# gpio_expander.net
KiCad netlist of a schematic drawn in EAGLE
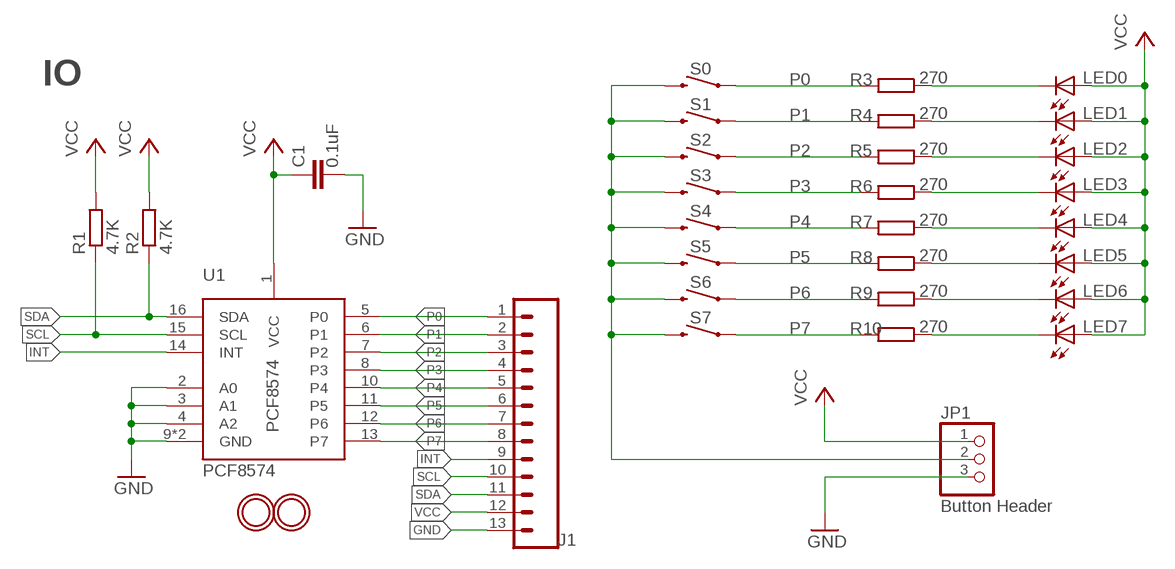
[diagram p0: schematic, sheet 1]

(export (version "E")
  (design (tool "Eeschema 10.0.6"))
  (components
    (comp (ref "C1")
      (value "0.1uF")
      (footprint "eagle-import:C0805K")
      (libsource (lib "eagle-import") (part "C-EUC0805K"))
    )
    (comp (ref "J1")
      (value "GPIO Expander Pins")
      (footprint "eagle-import:1X13_NO_SILK")
      (libsource (lib "eagle-import") (part "CONN_13"))
    )
    (comp (ref "JP1")
      (value "Button Header")
      (footprint "eagle-import:1X03")
      (libsource (lib "eagle-import") (part "PINHD-1X3"))
    )
    (comp (ref "LED0")
      (value "GREEN")
      (footprint "eagle-import:CHIP-LED0805")
      (libsource (lib "eagle-import") (part "LEDCHIP-LED0805"))
    )
    (comp (ref "LED1")
      (value "GREEN")
      (footprint "eagle-import:CHIP-LED0805")
      (libsource (lib "eagle-import") (part "LEDCHIP-LED0805"))
    )
    (comp (ref "LED2")
      (value "GREEN")
      (footprint "eagle-import:CHIP-LED0805")
      (libsource (lib "eagle-import") (part "LEDCHIP-LED0805"))
    )
    (comp (ref "LED3")
      (value "GREEN")
      (footprint "eagle-import:CHIP-LED0805")
      (libsource (lib "eagle-import") (part "LEDCHIP-LED0805"))
    )
    (comp (ref "LED4")
      (value "GREEN")
      (footprint "eagle-import:CHIP-LED0805")
      (libsource (lib "eagle-import") (part "LEDCHIP-LED0805"))
    )
    (comp (ref "LED5")
      (value "GREEN")
      (footprint "eagle-import:CHIP-LED0805")
      (libsource (lib "eagle-import") (part "LEDCHIP-LED0805"))
    )
    (comp (ref "LED6")
      (value "GREEN")
      (footprint "eagle-import:CHIP-LED0805")
      (libsource (lib "eagle-import") (part "LEDCHIP-LED0805"))
    )
    (comp (ref "LED7")
      (value "GREEN")
      (footprint "eagle-import:CHIP-LED0805")
      (libsource (lib "eagle-import") (part "LEDCHIP-LED0805"))
    )
    (comp (ref "MH1")
      (value "MOUNTINGHOLE2.5")
      (footprint "eagle-import:MOUNTINGHOLE_2.5_PLATED")
      (libsource (lib "eagle-import") (part "MOUNTINGHOLE2.5"))
    )
    (comp (ref "MH3")
      (value "MOUNTINGHOLE2.5")
      (footprint "eagle-import:MOUNTINGHOLE_2.5_PLATED")
      (libsource (lib "eagle-import") (part "MOUNTINGHOLE2.5"))
    )
    (comp (ref "R1")
      (value "4.7K")
      (footprint "eagle-import:R0805")
      (libsource (lib "eagle-import") (part "R-EU_R0805"))
    )
    (comp (ref "R2")
      (value "4.7K")
      (footprint "eagle-import:R0805")
      (libsource (lib "eagle-import") (part "R-EU_R0805"))
    )
    (comp (ref "R3")
      (value "270")
      (footprint "eagle-import:R0805")
      (libsource (lib "eagle-import") (part "R-EU_R0805"))
    )
    (comp (ref "R4")
      (value "270")
      (footprint "eagle-import:R0805")
      (libsource (lib "eagle-import") (part "R-EU_R0805"))
    )
    (comp (ref "R5")
      (value "270")
      (footprint "eagle-import:R0805")
      (libsource (lib "eagle-import") (part "R-EU_R0805"))
    )
    (comp (ref "R6")
      (value "270")
      (footprint "eagle-import:R0805")
      (libsource (lib "eagle-import") (part "R-EU_R0805"))
    )
    (comp (ref "R7")
      (value "270")
      (footprint "eagle-import:R0805")
      (libsource (lib "eagle-import") (part "R-EU_R0805"))
    )
    (comp (ref "R8")
      (value "270")
      (footprint "eagle-import:R0805")
      (libsource (lib "eagle-import") (part "R-EU_R0805"))
    )
    (comp (ref "R9")
      (value "270")
      (footprint "eagle-import:R0805")
      (libsource (lib "eagle-import") (part "R-EU_R0805"))
    )
    (comp (ref "R10")
      (value "270")
      (footprint "eagle-import:R0805")
      (libsource (lib "eagle-import") (part "R-EU_R0805"))
    )
    (comp (ref "S0")
      (value "MOMENTARY-SWITCH-SPST-SMD-4.6X2.8MM")
      (footprint "eagle-import:TACTILE_SWITCH_SMD_4.6X2.8MM")
      (libsource (lib "eagle-import") (part "MOMENTARY-SWITCH-SPST-SMD-4.6X2.8MM"))
    )
    (comp (ref "S1")
      (value "MOMENTARY-SWITCH-SPST-SMD-4.6X2.8MM")
      (footprint "eagle-import:TACTILE_SWITCH_SMD_4.6X2.8MM")
      (libsource (lib "eagle-import") (part "MOMENTARY-SWITCH-SPST-SMD-4.6X2.8MM"))
    )
    (comp (ref "S2")
      (value "MOMENTARY-SWITCH-SPST-SMD-4.6X2.8MM")
      (footprint "eagle-import:TACTILE_SWITCH_SMD_4.6X2.8MM")
      (libsource (lib "eagle-import") (part "MOMENTARY-SWITCH-SPST-SMD-4.6X2.8MM"))
    )
    (comp (ref "S3")
      (value "MOMENTARY-SWITCH-SPST-SMD-4.6X2.8MM")
      (footprint "eagle-import:TACTILE_SWITCH_SMD_4.6X2.8MM")
      (libsource (lib "eagle-import") (part "MOMENTARY-SWITCH-SPST-SMD-4.6X2.8MM"))
    )
    (comp (ref "S4")
      (value "MOMENTARY-SWITCH-SPST-SMD-4.6X2.8MM")
      (footprint "eagle-import:TACTILE_SWITCH_SMD_4.6X2.8MM")
      (libsource (lib "eagle-import") (part "MOMENTARY-SWITCH-SPST-SMD-4.6X2.8MM"))
    )
    (comp (ref "S5")
      (value "MOMENTARY-SWITCH-SPST-SMD-4.6X2.8MM")
      (footprint "eagle-import:TACTILE_SWITCH_SMD_4.6X2.8MM")
      (libsource (lib "eagle-import") (part "MOMENTARY-SWITCH-SPST-SMD-4.6X2.8MM"))
    )
    (comp (ref "S6")
      (value "MOMENTARY-SWITCH-SPST-SMD-4.6X2.8MM")
      (footprint "eagle-import:TACTILE_SWITCH_SMD_4.6X2.8MM")
      (libsource (lib "eagle-import") (part "MOMENTARY-SWITCH-SPST-SMD-4.6X2.8MM"))
    )
    (comp (ref "S7")
      (value "MOMENTARY-SWITCH-SPST-SMD-4.6X2.8MM")
      (footprint "eagle-import:TACTILE_SWITCH_SMD_4.6X2.8MM")
      (libsource (lib "eagle-import") (part "MOMENTARY-SWITCH-SPST-SMD-4.6X2.8MM"))
    )
    (comp (ref "U1")
      (value "PCF8574")
      (footprint "eagle-import:QFN-16-3MM")
      (libsource (lib "eagle-import") (part "PCF8574"))
    )
  )
  (nets
    (net (code "1") (name "GND") (class "Default")
      (node (ref "C1") (pin "2") (pinfunction "2_2") (pintype "passive"))
      (node (ref "J1") (pin "13") (pinfunction "13_13") (pintype "passive"))
      (node (ref "JP1") (pin "3") (pinfunction "3_3") (pintype "passive"))
      (node (ref "U1") (pin "2") (pinfunction "A0_2") (pintype "bidirectional"))
      (node (ref "U1") (pin "3") (pinfunction "A1_3") (pintype "bidirectional"))
      (node (ref "U1") (pin "4") (pinfunction "A2_4") (pintype "bidirectional"))
      (node (ref "U1") (pin "9") (pinfunction "GND_9") (pintype "bidirectional"))
      (node (ref "U1") (pin "P$1") (pinfunction "GND_P$1") (pintype "bidirectional"))
    )
    (net (code "2") (name "INT") (class "Default")
      (node (ref "J1") (pin "9") (pinfunction "9_9") (pintype "passive"))
      (node (ref "U1") (pin "14") (pinfunction "INT_14") (pintype "bidirectional"))
    )
    (net (code "3") (name "Net-(JP1-Pad2)") (class "Default")
      (node (ref "JP1") (pin "2") (pinfunction "2_2") (pintype "passive"))
      (node (ref "S0") (pin "3") (pinfunction "2_3") (pintype "passive"))
      (node (ref "S0") (pin "4") (pinfunction "2_4") (pintype "passive"))
      (node (ref "S1") (pin "3") (pinfunction "2_3") (pintype "passive"))
      (node (ref "S1") (pin "4") (pinfunction "2_4") (pintype "passive"))
      (node (ref "S2") (pin "3") (pinfunction "2_3") (pintype "passive"))
      (node (ref "S2") (pin "4") (pinfunction "2_4") (pintype "passive"))
      (node (ref "S3") (pin "3") (pinfunction "2_3") (pintype "passive"))
      (node (ref "S3") (pin "4") (pinfunction "2_4") (pintype "passive"))
      (node (ref "S4") (pin "3") (pinfunction "2_3") (pintype "passive"))
      (node (ref "S4") (pin "4") (pinfunction "2_4") (pintype "passive"))
      (node (ref "S5") (pin "3") (pinfunction "2_3") (pintype "passive"))
      (node (ref "S5") (pin "4") (pinfunction "2_4") (pintype "passive"))
      (node (ref "S6") (pin "3") (pinfunction "2_3") (pintype "passive"))
      (node (ref "S6") (pin "4") (pinfunction "2_4") (pintype "passive"))
      (node (ref "S7") (pin "3") (pinfunction "2_3") (pintype "passive"))
      (node (ref "S7") (pin "4") (pinfunction "2_4") (pintype "passive"))
    )
    (net (code "4") (name "Net-(LED0-PadC)") (class "Default")
      (node (ref "LED0") (pin "C") (pinfunction "C_C") (pintype "passive"))
      (node (ref "R3") (pin "1") (pinfunction "1_1") (pintype "passive"))
    )
    (net (code "5") (name "Net-(LED1-PadC)") (class "Default")
      (node (ref "LED1") (pin "C") (pinfunction "C_C") (pintype "passive"))
      (node (ref "R4") (pin "1") (pinfunction "1_1") (pintype "passive"))
    )
    (net (code "6") (name "Net-(LED2-PadC)") (class "Default")
      (node (ref "LED2") (pin "C") (pinfunction "C_C") (pintype "passive"))
      (node (ref "R5") (pin "1") (pinfunction "1_1") (pintype "passive"))
    )
    (net (code "7") (name "Net-(LED3-PadC)") (class "Default")
      (node (ref "LED3") (pin "C") (pinfunction "C_C") (pintype "passive"))
      (node (ref "R6") (pin "1") (pinfunction "1_1") (pintype "passive"))
    )
    (net (code "8") (name "Net-(LED4-PadC)") (class "Default")
      (node (ref "LED4") (pin "C") (pinfunction "C_C") (pintype "passive"))
      (node (ref "R7") (pin "1") (pinfunction "1_1") (pintype "passive"))
    )
    (net (code "9") (name "Net-(LED5-PadC)") (class "Default")
      (node (ref "LED5") (pin "C") (pinfunction "C_C") (pintype "passive"))
      (node (ref "R8") (pin "1") (pinfunction "1_1") (pintype "passive"))
    )
    (net (code "10") (name "Net-(LED6-PadC)") (class "Default")
      (node (ref "LED6") (pin "C") (pinfunction "C_C") (pintype "passive"))
      (node (ref "R9") (pin "1") (pinfunction "1_1") (pintype "passive"))
    )
    (net (code "11") (name "Net-(LED7-PadC)") (class "Default")
      (node (ref "LED7") (pin "C") (pinfunction "C_C") (pintype "passive"))
      (node (ref "R10") (pin "1") (pinfunction "1_1") (pintype "passive"))
    )
    (net (code "12") (name "P0") (class "Default")
      (node (ref "J1") (pin "1") (pinfunction "1_1") (pintype "passive"))
      (node (ref "R3") (pin "2") (pinfunction "2_2") (pintype "passive"))
      (node (ref "S0") (pin "1") (pinfunction "1_1") (pintype "passive"))
      (node (ref "S0") (pin "2") (pinfunction "1_2") (pintype "passive"))
      (node (ref "U1") (pin "5") (pinfunction "P0_5") (pintype "bidirectional"))
    )
    (net (code "13") (name "P1") (class "Default")
      (node (ref "J1") (pin "2") (pinfunction "2_2") (pintype "passive"))
      (node (ref "R4") (pin "2") (pinfunction "2_2") (pintype "passive"))
      (node (ref "S1") (pin "1") (pinfunction "1_1") (pintype "passive"))
      (node (ref "S1") (pin "2") (pinfunction "1_2") (pintype "passive"))
      (node (ref "U1") (pin "6") (pinfunction "P1_6") (pintype "bidirectional"))
    )
    (net (code "14") (name "P2") (class "Default")
      (node (ref "J1") (pin "3") (pinfunction "3_3") (pintype "passive"))
      (node (ref "R5") (pin "2") (pinfunction "2_2") (pintype "passive"))
      (node (ref "S2") (pin "1") (pinfunction "1_1") (pintype "passive"))
      (node (ref "S2") (pin "2") (pinfunction "1_2") (pintype "passive"))
      (node (ref "U1") (pin "7") (pinfunction "P2_7") (pintype "bidirectional"))
    )
    (net (code "15") (name "P3") (class "Default")
      (node (ref "J1") (pin "4") (pinfunction "4_4") (pintype "passive"))
      (node (ref "R6") (pin "2") (pinfunction "2_2") (pintype "passive"))
      (node (ref "S3") (pin "1") (pinfunction "1_1") (pintype "passive"))
      (node (ref "S3") (pin "2") (pinfunction "1_2") (pintype "passive"))
      (node (ref "U1") (pin "8") (pinfunction "P3_8") (pintype "bidirectional"))
    )
    (net (code "16") (name "P4") (class "Default")
      (node (ref "J1") (pin "5") (pinfunction "5_5") (pintype "passive"))
      (node (ref "R7") (pin "2") (pinfunction "2_2") (pintype "passive"))
      (node (ref "S4") (pin "1") (pinfunction "1_1") (pintype "passive"))
      (node (ref "S4") (pin "2") (pinfunction "1_2") (pintype "passive"))
      (node (ref "U1") (pin "10") (pinfunction "P4_10") (pintype "bidirectional"))
    )
    (net (code "17") (name "P5") (class "Default")
      (node (ref "J1") (pin "6") (pinfunction "6_6") (pintype "passive"))
      (node (ref "R8") (pin "2") (pinfunction "2_2") (pintype "passive"))
      (node (ref "S5") (pin "1") (pinfunction "1_1") (pintype "passive"))
      (node (ref "S5") (pin "2") (pinfunction "1_2") (pintype "passive"))
      (node (ref "U1") (pin "11") (pinfunction "P5_11") (pintype "bidirectional"))
    )
    (net (code "18") (name "P6") (class "Default")
      (node (ref "J1") (pin "7") (pinfunction "7_7") (pintype "passive"))
      (node (ref "R9") (pin "2") (pinfunction "2_2") (pintype "passive"))
      (node (ref "S6") (pin "1") (pinfunction "1_1") (pintype "passive"))
      (node (ref "S6") (pin "2") (pinfunction "1_2") (pintype "passive"))
      (node (ref "U1") (pin "12") (pinfunction "P6_12") (pintype "bidirectional"))
    )
    (net (code "19") (name "P7") (class "Default")
      (node (ref "J1") (pin "8") (pinfunction "8_8") (pintype "passive"))
      (node (ref "R10") (pin "2") (pinfunction "2_2") (pintype "passive"))
      (node (ref "S7") (pin "1") (pinfunction "1_1") (pintype "passive"))
      (node (ref "S7") (pin "2") (pinfunction "1_2") (pintype "passive"))
      (node (ref "U1") (pin "13") (pinfunction "P7_13") (pintype "bidirectional"))
    )
    (net (code "20") (name "SCL") (class "Default")
      (node (ref "J1") (pin "10") (pinfunction "10_10") (pintype "passive"))
      (node (ref "R1") (pin "1") (pinfunction "1_1") (pintype "passive"))
      (node (ref "U1") (pin "15") (pinfunction "SCL_15") (pintype "bidirectional"))
    )
    (net (code "21") (name "SDA") (class "Default")
      (node (ref "J1") (pin "11") (pinfunction "11_11") (pintype "passive"))
      (node (ref "R2") (pin "1") (pinfunction "1_1") (pintype "passive"))
      (node (ref "U1") (pin "16") (pinfunction "SDA_16") (pintype "bidirectional"))
    )
    (net (code "22") (name "VCC") (class "Default")
      (node (ref "C1") (pin "1") (pinfunction "1_1") (pintype "passive"))
      (node (ref "J1") (pin "12") (pinfunction "12_12") (pintype "passive"))
      (node (ref "JP1") (pin "1") (pinfunction "1_1") (pintype "passive"))
      (node (ref "LED0") (pin "A") (pinfunction "A_A") (pintype "passive"))
      (node (ref "LED1") (pin "A") (pinfunction "A_A") (pintype "passive"))
      (node (ref "LED2") (pin "A") (pinfunction "A_A") (pintype "passive"))
      (node (ref "LED3") (pin "A") (pinfunction "A_A") (pintype "passive"))
      (node (ref "LED4") (pin "A") (pinfunction "A_A") (pintype "passive"))
      (node (ref "LED5") (pin "A") (pinfunction "A_A") (pintype "passive"))
      (node (ref "LED6") (pin "A") (pinfunction "A_A") (pintype "passive"))
      (node (ref "LED7") (pin "A") (pinfunction "A_A") (pintype "passive"))
      (node (ref "R1") (pin "2") (pinfunction "2_2") (pintype "passive"))
      (node (ref "R2") (pin "2") (pinfunction "2_2") (pintype "passive"))
      (node (ref "U1") (pin "1") (pinfunction "VCC_1") (pintype "bidirectional"))
    )
  )
)
